# 06_-_JTAG.net
KiCad netlist of a schematic drawn in Altium Designer
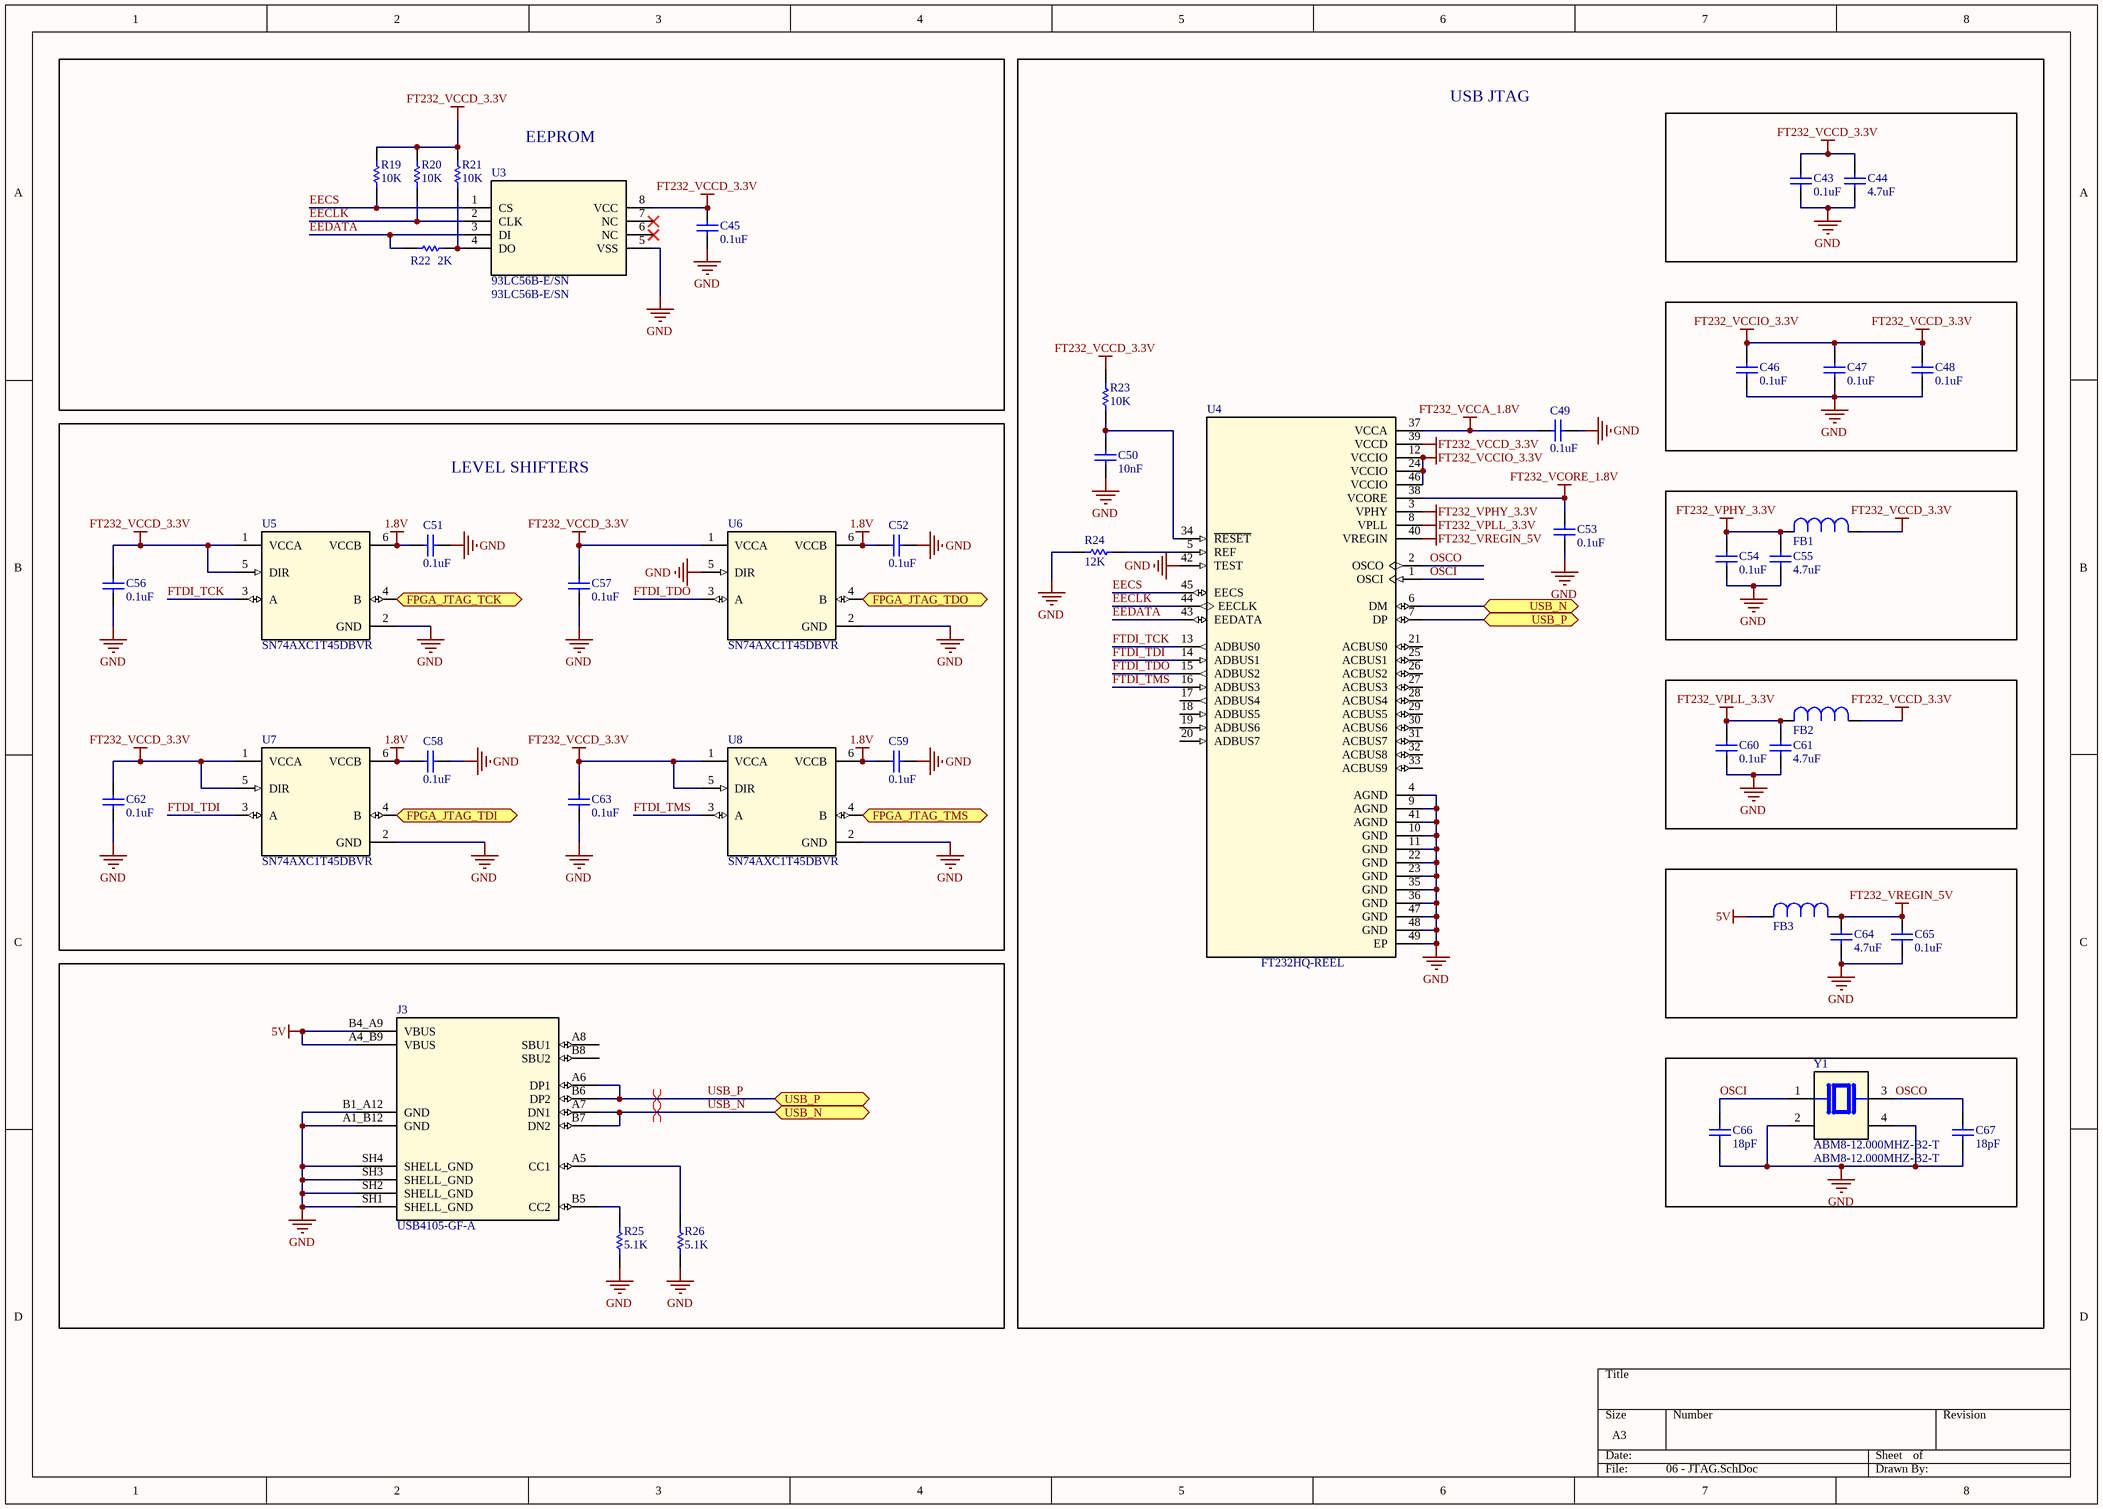
[diagram p0: 06 - JTAG.SchDoc]

(export (version "E")
  (design (tool "Eeschema 10.0.6"))
  (components
    (comp (ref "C43")
      (value "0.1uF")
      (footprint "0402-C-R")
      (description "0.1 µF ±10% 25V Ceramic Capacitor X5R 0402 (1005 Metric)")
      (fields (field (name "VOLTAGE") "25V") (field (name "TOLERANCE") "10%"))
      (libsource (lib "Schlib") (part "CAP CER 0.1UF 25V X5R 0402"))
    )
    (comp (ref "C44")
      (value "4.7uF")
      (footprint "0402-C-R")
      (description "CAP SMD 0402 MLCC GERAL 4.7uF 25V ±20% 0402 X5s PN: GRM155D81C475ME15J MURATA")
      (fields (field (name "VOLTAGE") "25V") (field (name "TOLERANCE") "20%"))
      (libsource (lib "Schlib") (part "CAP CER 4.7UF 10V X5R 0402"))
    )
    (comp (ref "C45")
      (value "0.1uF")
      (footprint "0402-C-R")
      (description "0.1 µF ±10% 25V Ceramic Capacitor X5R 0402 (1005 Metric)")
      (fields (field (name "VOLTAGE") "25V") (field (name "TOLERANCE") "10%"))
      (libsource (lib "Schlib") (part "CAP CER 0.1UF 25V X5R 0402"))
    )
    (comp (ref "C46")
      (value "0.1uF")
      (footprint "0402-C-R")
      (description "0.1 µF ±10% 25V Ceramic Capacitor X5R 0402 (1005 Metric)")
      (fields (field (name "VOLTAGE") "25V") (field (name "TOLERANCE") "10%"))
      (libsource (lib "Schlib") (part "CAP CER 0.1UF 25V X5R 0402"))
    )
    (comp (ref "C47")
      (value "0.1uF")
      (footprint "0402-C-R")
      (description "0.1 µF ±10% 25V Ceramic Capacitor X5R 0402 (1005 Metric)")
      (fields (field (name "VOLTAGE") "25V") (field (name "TOLERANCE") "10%"))
      (libsource (lib "Schlib") (part "CAP CER 0.1UF 25V X5R 0402"))
    )
    (comp (ref "C48")
      (value "0.1uF")
      (footprint "0402-C-R")
      (description "0.1 µF ±10% 25V Ceramic Capacitor X5R 0402 (1005 Metric)")
      (fields (field (name "VOLTAGE") "25V") (field (name "TOLERANCE") "10%"))
      (libsource (lib "Schlib") (part "CAP CER 0.1UF 25V X5R 0402"))
    )
    (comp (ref "C49")
      (value "0.1uF")
      (footprint "0402-C-R")
      (description "0.1 µF ±10% 25V Ceramic Capacitor X5R 0402 (1005 Metric)")
      (fields (field (name "VOLTAGE") "25V") (field (name "TOLERANCE") "10%"))
      (libsource (lib "Schlib") (part "CAP CER 0.1UF 25V X5R 0402"))
    )
    (comp (ref "C50")
      (value "10nF")
      (footprint "0402-C-R")
      (description "10000 pF ±10% 25V Ceramic Capacitor X7R 0402 (1005 Metric)")
      (fields (field (name "VOLTAGE") "25V") (field (name "TOLERANCE") "10%"))
      (libsource (lib "Schlib") (part "CAP CER 10nF 25V X7R 0402"))
    )
    (comp (ref "C51")
      (value "0.1uF")
      (footprint "0402-C-R")
      (description "0.1 µF ±10% 25V Ceramic Capacitor X5R 0402 (1005 Metric)")
      (fields (field (name "VOLTAGE") "25V") (field (name "TOLERANCE") "10%"))
      (libsource (lib "Schlib") (part "CAP CER 0.1UF 25V X5R 0402"))
    )
    (comp (ref "C52")
      (value "0.1uF")
      (footprint "0402-C-R")
      (description "0.1 µF ±10% 25V Ceramic Capacitor X5R 0402 (1005 Metric)")
      (fields (field (name "VOLTAGE") "25V") (field (name "TOLERANCE") "10%"))
      (libsource (lib "Schlib") (part "CAP CER 0.1UF 25V X5R 0402"))
    )
    (comp (ref "C53")
      (value "0.1uF")
      (footprint "0402-C-R")
      (description "0.1 µF ±10% 25V Ceramic Capacitor X5R 0402 (1005 Metric)")
      (fields (field (name "VOLTAGE") "25V") (field (name "TOLERANCE") "10%"))
      (libsource (lib "Schlib") (part "CAP CER 0.1UF 25V X5R 0402"))
    )
    (comp (ref "C54")
      (value "0.1uF")
      (footprint "0402-C-R")
      (description "0.1 µF ±10% 25V Ceramic Capacitor X5R 0402 (1005 Metric)")
      (fields (field (name "VOLTAGE") "25V") (field (name "TOLERANCE") "10%"))
      (libsource (lib "Schlib") (part "CAP CER 0.1UF 25V X5R 0402"))
    )
    (comp (ref "C55")
      (value "4.7uF")
      (footprint "0402-C-R")
      (description "CAP SMD 0402 MLCC GERAL 4.7uF 25V ±20% 0402 X5s PN: GRM155D81C475ME15J MURATA")
      (fields (field (name "VOLTAGE") "25V") (field (name "TOLERANCE") "20%"))
      (libsource (lib "Schlib") (part "CAP CER 4.7UF 25V X5R 0402"))
    )
    (comp (ref "C56")
      (value "0.1uF")
      (footprint "0402-C-R")
      (description "0.1 µF ±10% 25V Ceramic Capacitor X5R 0402 (1005 Metric)")
      (fields (field (name "VOLTAGE") "25V") (field (name "TOLERANCE") "10%"))
      (libsource (lib "Schlib") (part "CAP CER 0.1UF 25V X5R 0402"))
    )
    (comp (ref "C57")
      (value "0.1uF")
      (footprint "0402-C-R")
      (description "0.1 µF ±10% 25V Ceramic Capacitor X5R 0402 (1005 Metric)")
      (fields (field (name "VOLTAGE") "25V") (field (name "TOLERANCE") "10%"))
      (libsource (lib "Schlib") (part "CAP CER 0.1UF 25V X5R 0402"))
    )
    (comp (ref "C58")
      (value "0.1uF")
      (footprint "0402-C-R")
      (description "0.1 µF ±10% 25V Ceramic Capacitor X5R 0402 (1005 Metric)")
      (fields (field (name "VOLTAGE") "25V") (field (name "TOLERANCE") "10%"))
      (libsource (lib "Schlib") (part "CAP CER 0.1UF 25V X5R 0402"))
    )
    (comp (ref "C59")
      (value "0.1uF")
      (footprint "0402-C-R")
      (description "0.1 µF ±10% 25V Ceramic Capacitor X5R 0402 (1005 Metric)")
      (fields (field (name "VOLTAGE") "25V") (field (name "TOLERANCE") "10%"))
      (libsource (lib "Schlib") (part "CAP CER 0.1UF 25V X5R 0402"))
    )
    (comp (ref "C60")
      (value "0.1uF")
      (footprint "0402-C-R")
      (description "0.1 µF ±10% 25V Ceramic Capacitor X5R 0402 (1005 Metric)")
      (fields (field (name "VOLTAGE") "25V") (field (name "TOLERANCE") "10%"))
      (libsource (lib "Schlib") (part "CAP CER 0.1UF 25V X5R 0402"))
    )
    (comp (ref "C61")
      (value "4.7uF")
      (footprint "0402-C-R")
      (description "CAP SMD 0402 MLCC GERAL 4.7uF 25V ±20% 0402 X5s PN: GRM155D81C475ME15J MURATA")
      (fields (field (name "VOLTAGE") "25V") (field (name "TOLERANCE") "20%"))
      (libsource (lib "Schlib") (part "CAP CER 4.7UF 25V X5R 0402"))
    )
    (comp (ref "C62")
      (value "0.1uF")
      (footprint "0402-C-R")
      (description "0.1 µF ±10% 25V Ceramic Capacitor X5R 0402 (1005 Metric)")
      (fields (field (name "VOLTAGE") "25V") (field (name "TOLERANCE") "10%"))
      (libsource (lib "Schlib") (part "CAP CER 0.1UF 25V X5R 0402"))
    )
    (comp (ref "C63")
      (value "0.1uF")
      (footprint "0402-C-R")
      (description "0.1 µF ±10% 25V Ceramic Capacitor X5R 0402 (1005 Metric)")
      (fields (field (name "VOLTAGE") "25V") (field (name "TOLERANCE") "10%"))
      (libsource (lib "Schlib") (part "CAP CER 0.1UF 25V X5R 0402"))
    )
    (comp (ref "C64")
      (value "4.7uF")
      (footprint "0402-C-R")
      (description "CAP SMD 0402 MLCC GERAL 4.7uF 25V ±20% 0402 X5s PN: GRM155D81C475ME15J MURATA")
      (fields (field (name "VOLTAGE") "25V") (field (name "TOLERANCE") "20%"))
      (libsource (lib "Schlib") (part "CAP CER 4.7UF 25V X5R 0402"))
    )
    (comp (ref "C65")
      (value "0.1uF")
      (footprint "0402-C-R")
      (description "0.1 µF ±10% 25V Ceramic Capacitor X5R 0402 (1005 Metric)")
      (fields (field (name "VOLTAGE") "25V") (field (name "TOLERANCE") "10%"))
      (libsource (lib "Schlib") (part "CAP CER 0.1UF 25V X5R 0402"))
    )
    (comp (ref "C66")
      (value "18pF")
      (footprint "0402-C-R")
      (description "18 pF ±5% 50V Capacitor de cerâmica C0G, NP0 0402 (métrico 1005)PN:GRM1555C1H180JA01D MURATA")
      (fields (field (name "VOLTAGE") "50V") (field (name "TOLERANCE") "5%"))
      (libsource (lib "Schlib") (part "CAP CER 18PF 50V C0G/NP0 0402"))
    )
    (comp (ref "C67")
      (value "18pF")
      (footprint "0402-C-R")
      (description "18 pF ±5% 50V Capacitor de cerâmica C0G, NP0 0402 (métrico 1005)PN:GRM1555C1H180JA01D MURATA")
      (fields (field (name "VOLTAGE") "50V") (field (name "TOLERANCE") "5%"))
      (libsource (lib "Schlib") (part "CAP CER 18PF 50V C0G/NP0 0402"))
    )
    (comp (ref "FB1")
      (value "BLM15HD182SN1D")
      (footprint "0402-F-R")
      (description "FERRITE BEAD 1.8K OHM 0402 1LN PN: BLM15HD182SN1D")
      (libsource (lib "Schlib") (part "FERRITE BEAD 1.8K OHM 0402 1LN"))
    )
    (comp (ref "FB2")
      (value "BLM15HD182SN1D")
      (footprint "0402-F-R")
      (description "FERRITE BEAD 1.8K OHM 0402 1LN PN: BLM15HD182SN1D")
      (libsource (lib "Schlib") (part "FERRITE BEAD 1.8K OHM 0402 1LN"))
    )
    (comp (ref "FB3")
      (value "BLM15HD182SN1D")
      (footprint "0402-F-R")
      (description "FERRITE BEAD 1.8K OHM 0402 1LN PN: BLM15HD182SN1D")
      (libsource (lib "Schlib") (part "FERRITE BEAD 1.8K OHM 0402 1LN"))
    )
    (comp (ref "J3")
      (value "CONN RCP USB2.0 TYP C 24P SMD RA")
      (footprint "GCT_USB4105-GF-A")
      (description "CONN RCP USB2.0 TYP C 24P SMD RA PN: USB4105-GF-A")
      (fields (field (name "MF") "{'manufacturer': u'GCT'}") (field (name "PN") "USB4105-GF-A"))
      (libsource (lib "Schlib") (part "CONN RCP USB2.0 TYP C 24P SMD RA"))
    )
    (comp (ref "R19")
      (value "10K")
      (footprint "0402-R-R")
      (description "10 kOhms ±1% 0,063W, 1/16W Resistor de chip 0402 (métrico 1005) Resistente à umidade Filme grosso")
      (fields (field (name "POWER") "0.063W") (field (name "TOLERANCE") "1%"))
      (libsource (lib "Schlib") (part "RES 10K OHM 1% 1/16W 0402"))
    )
    (comp (ref "R20")
      (value "10K")
      (footprint "0402-R-R")
      (description "10 kOhms ±1% 0,063W, 1/16W Resistor de chip 0402 (métrico 1005) Resistente à umidade Filme grosso")
      (fields (field (name "POWER") "0.063W") (field (name "TOLERANCE") "1%"))
      (libsource (lib "Schlib") (part "RES 10K OHM 1% 1/16W 0402"))
    )
    (comp (ref "R21")
      (value "10K")
      (footprint "0402-R-R")
      (description "10 kOhms ±1% 0,063W, 1/16W Resistor de chip 0402 (métrico 1005) Resistente à umidade Filme grosso")
      (fields (field (name "POWER") "0.063W") (field (name "TOLERANCE") "1%"))
      (libsource (lib "Schlib") (part "RES 10K OHM 1% 1/16W 0402"))
    )
    (comp (ref "R22")
      (value "2K")
      (footprint "0402-R-R")
      (description "RES SMD GERAL FILM 2K 0.063W ±1% 0402 7\" TAPE PN: RMCF0402FT2K00 STACKPOLE")
      (fields (field (name "POWER") "0.063W") (field (name "TOLERANCE") "1%"))
      (libsource (lib "Schlib") (part "RES SMD 0402 2K 0.063W ±1%"))
    )
    (comp (ref "R23")
      (value "10K")
      (footprint "0402-R-R")
      (description "10 kOhms ±1% 0,063W, 1/16W Resistor de chip 0402 (métrico 1005) Resistente à umidade Filme grosso")
      (fields (field (name "POWER") "0.063W") (field (name "TOLERANCE") "1%"))
      (libsource (lib "Schlib") (part "RES 10K OHM 1% 1/16W 0402"))
    )
    (comp (ref "R24")
      (value "12K")
      (footprint "0402-R-R")
      (description "RES SMD GERAL FILM 12K 0.063W ±1% 0402 7\" TAPE PN: RMCF0402FT12K0")
      (fields (field (name "POWER") "0.063W") (field (name "TOLERANCE") "1%"))
      (libsource (lib "Schlib") (part "RES SMD 0402 12K 0.063W ±1%"))
    )
    (comp (ref "R25")
      (value "5.1K")
      (footprint "0402-R-R")
      (description "RES SMD 0402 5.1K OHM 1% 1/16W 0402 PN: RMCF0402FT5K10")
      (fields (field (name "TOLERANCE") "0.1%") (field (name "POWER") "0.063W"))
      (libsource (lib "Schlib") (part "RES SMD 0402 5.1K OHM 1% 1/16W"))
    )
    (comp (ref "R26")
      (value "5.1K")
      (footprint "0402-R-R")
      (description "RES SMD 0402 5.1K OHM 1% 1/16W 0402 PN: RMCF0402FT5K10")
      (fields (field (name "TOLERANCE") "0.1%") (field (name "POWER") "0.063W"))
      (libsource (lib "Schlib") (part "RES SMD 0402 5.1K OHM 1% 1/16W"))
    )
    (comp (ref "U3")
      (value "93LC56B-E/SN")
      (footprint "93LC56B-E/SN")
      (description "EEPROM CI de memória 2Kbit Microwire 2 MHz 8-SOIC. PN: 93LC56B-E/SN")
      (fields (field (name "PN") "93LC56B-E/SN"))
      (libsource (lib "Schlib") (part "IC EEPROM 2KBIT MICROWIRE 8SOIC"))
    )
    (comp (ref "U4")
      (value "IC HS USB TO UART/FIFO 48QFN")
      (footprint "FT232HQ")
      (description "USB Bridge, USB to UART,FIFO USB 2.0 UART, FIFO Interface 48-QFN (8x8) PN: FT232HQ-REEL")
      (fields
        (field (name "MP") "FT232HQ-REEL")
        (field (name "MF") "FTDI, Future")
        (field (name "PN") "FT232HQ-REEL")
      )
      (libsource (lib "Schlib") (part "IC HS USB TO UART/FIFO 48QFN"))
    )
    (comp (ref "U5")
      (value "SN74AXC1T45DBVR")
      (footprint "SN74AXC1T45DBVR")
      (description "Nível de tensão Tradutor Bidirecional 1 Circuito 1 Canal 500Mbps SOT-23-6. PN: SN74AXC1T45DBVR")
      (fields (field (name "MF") "Texas Instruments") (field (name "PN") "SN74AXC1T45DBVR"))
      (libsource (lib "Schlib") (part "IC TRANSLATOR BIDIR SOT23-6"))
    )
    (comp (ref "U6")
      (value "SN74AXC1T45DBVR")
      (footprint "SN74AXC1T45DBVR")
      (description "Nível de tensão Tradutor Bidirecional 1 Circuito 1 Canal 500Mbps SOT-23-6. PN: SN74AXC1T45DBVR")
      (fields (field (name "MF") "Texas Instruments") (field (name "PN") "SN74AXC1T45DBVR"))
      (libsource (lib "Schlib") (part "IC TRANSLATOR BIDIR SOT23-6"))
    )
    (comp (ref "U7")
      (value "SN74AXC1T45DBVR")
      (footprint "SN74AXC1T45DBVR")
      (description "Nível de tensão Tradutor Bidirecional 1 Circuito 1 Canal 500Mbps SOT-23-6. PN: SN74AXC1T45DBVR")
      (fields (field (name "MF") "Texas Instruments") (field (name "PN") "SN74AXC1T45DBVR"))
      (libsource (lib "Schlib") (part "IC TRANSLATOR BIDIR SOT23-6"))
    )
    (comp (ref "U8")
      (value "SN74AXC1T45DBVR")
      (footprint "SN74AXC1T45DBVR")
      (description "Nível de tensão Tradutor Bidirecional 1 Circuito 1 Canal 500Mbps SOT-23-6. PN: SN74AXC1T45DBVR")
      (fields (field (name "MF") "Texas Instruments") (field (name "PN") "SN74AXC1T45DBVR"))
      (libsource (lib "Schlib") (part "IC TRANSLATOR BIDIR SOT23-6"))
    )
    (comp (ref "Y1")
      (value "ABM8-12.000MHZ-B2-T")
      (footprint "XTAL_ABM8-12.000MHZ-B2-T")
      (description "12 MHz ±20ppm Cristal 18pF 120 Ohms 4-SMD, sem condutores PN: ABM8-12.000MHZ-B2-T")
      (fields (field (name "MF") "Abracon") (field (name "PN") "ABM8-12.000MHZ-B2-T"))
      (libsource (lib "Schlib") (part "CRYSTAL 12.0000MHZ 18PF SMD"))
    )
  )
  (nets
    (net (code "1") (name "/EECLK") (class "Default")
      (node (ref "R20") (pin "1") (pinfunction "1_1") (pintype "passive"))
      (node (ref "U3") (pin "2") (pinfunction "CLK_2") (pintype "passive"))
      (node (ref "U4") (pin "44") (pinfunction "EECLK_44") (pintype "output"))
    )
    (net (code "2") (name "/EECS") (class "Default")
      (node (ref "R19") (pin "1") (pinfunction "1_1") (pintype "passive"))
      (node (ref "U3") (pin "1") (pinfunction "CS_1") (pintype "passive"))
      (node (ref "U4") (pin "45") (pinfunction "EECS_45") (pintype "bidirectional"))
    )
    (net (code "3") (name "/EEDATA") (class "Default")
      (node (ref "R22") (pin "1") (pinfunction "1_1") (pintype "passive"))
      (node (ref "U3") (pin "3") (pinfunction "DI_3") (pintype "passive"))
      (node (ref "U4") (pin "43") (pinfunction "EEDATA_43") (pintype "bidirectional"))
    )
    (net (code "4") (name "/FPGA_JTAG_TCK") (class "Default")
      (node (ref "U5") (pin "4") (pinfunction "B_4") (pintype "bidirectional"))
    )
    (net (code "5") (name "/FPGA_JTAG_TDI") (class "Default")
      (node (ref "U7") (pin "4") (pinfunction "B_4") (pintype "bidirectional"))
    )
    (net (code "6") (name "/FPGA_JTAG_TDO") (class "Default")
      (node (ref "U6") (pin "4") (pinfunction "B_4") (pintype "bidirectional"))
    )
    (net (code "7") (name "/FPGA_JTAG_TMS") (class "Default")
      (node (ref "U8") (pin "4") (pinfunction "B_4") (pintype "bidirectional"))
    )
    (net (code "8") (name "/FTDI_TCK") (class "Default")
      (node (ref "U4") (pin "13") (pinfunction "ADBUS0_13") (pintype "output"))
      (node (ref "U5") (pin "3") (pinfunction "A_3") (pintype "bidirectional"))
    )
    (net (code "9") (name "/FTDI_TDI") (class "Default")
      (node (ref "U4") (pin "14") (pinfunction "ADBUS1_14") (pintype "input"))
      (node (ref "U7") (pin "3") (pinfunction "A_3") (pintype "bidirectional"))
    )
    (net (code "10") (name "/FTDI_TDO") (class "Default")
      (node (ref "U4") (pin "15") (pinfunction "ADBUS2_15") (pintype "output"))
      (node (ref "U6") (pin "3") (pinfunction "A_3") (pintype "bidirectional"))
    )
    (net (code "11") (name "/FTDI_TMS") (class "Default")
      (node (ref "U4") (pin "16") (pinfunction "ADBUS3_16") (pintype "input"))
      (node (ref "U8") (pin "3") (pinfunction "A_3") (pintype "bidirectional"))
    )
    (net (code "12") (name "/OSCI") (class "Default")
      (node (ref "C66") (pin "2") (pinfunction "2_2") (pintype "passive"))
      (node (ref "U4") (pin "1") (pinfunction "OSCI_1") (pintype "input"))
      (node (ref "Y1") (pin "1") (pinfunction "1_1") (pintype "passive"))
    )
    (net (code "13") (name "/OSCO") (class "Default")
      (node (ref "C67") (pin "2") (pinfunction "2_2") (pintype "passive"))
      (node (ref "U4") (pin "2") (pinfunction "OSCO_2") (pintype "output"))
      (node (ref "Y1") (pin "3") (pinfunction "2_3") (pintype "passive"))
    )
    (net (code "14") (name "/USB_N") (class "Default")
      (node (ref "J3") (pin "A7") (pinfunction "DN1_A7") (pintype "bidirectional"))
      (node (ref "J3") (pin "B7") (pinfunction "DN2_B7") (pintype "bidirectional"))
      (node (ref "U4") (pin "6") (pinfunction "DM_6") (pintype "bidirectional"))
    )
    (net (code "15") (name "/USB_P") (class "Default")
      (node (ref "J3") (pin "A6") (pinfunction "DP1_A6") (pintype "bidirectional"))
      (node (ref "J3") (pin "B6") (pinfunction "DP2_B6") (pintype "bidirectional"))
      (node (ref "U4") (pin "7") (pinfunction "DP_7") (pintype "bidirectional"))
    )
    (net (code "16") (name "1.8V") (class "Default")
      (node (ref "C51") (pin "2") (pinfunction "2_2") (pintype "passive"))
      (node (ref "C52") (pin "2") (pinfunction "2_2") (pintype "passive"))
      (node (ref "C58") (pin "2") (pinfunction "2_2") (pintype "passive"))
      (node (ref "C59") (pin "2") (pinfunction "2_2") (pintype "passive"))
      (node (ref "U5") (pin "6") (pinfunction "VCCB_6") (pintype "power_in"))
      (node (ref "U6") (pin "6") (pinfunction "VCCB_6") (pintype "power_in"))
      (node (ref "U7") (pin "6") (pinfunction "VCCB_6") (pintype "power_in"))
      (node (ref "U8") (pin "6") (pinfunction "VCCB_6") (pintype "power_in"))
    )
    (net (code "17") (name "5V") (class "Default")
      (node (ref "FB3") (pin "2") (pinfunction "2_2") (pintype "passive"))
      (node (ref "J3") (pin "A4_B9") (pinfunction "VBUS_A4_B9") (pintype "power_in"))
      (node (ref "J3") (pin "B4_A9") (pinfunction "VBUS_B4_A9") (pintype "power_in"))
    )
    (net (code "18") (name "FT232_VCCA_1.8V") (class "Default")
      (node (ref "C49") (pin "2") (pinfunction "2_2") (pintype "passive"))
      (node (ref "U4") (pin "37") (pinfunction "VCCA_37") (pintype "power_in"))
    )
    (net (code "19") (name "FT232_VCCD_3.3V") (class "Default")
      (node (ref "C43") (pin "2") (pinfunction "2_2") (pintype "passive"))
      (node (ref "C44") (pin "2") (pinfunction "2_2") (pintype "passive"))
      (node (ref "C45") (pin "2") (pinfunction "2_2") (pintype "passive"))
      (node (ref "C46") (pin "2") (pinfunction "2_2") (pintype "passive"))
      (node (ref "C47") (pin "2") (pinfunction "2_2") (pintype "passive"))
      (node (ref "C48") (pin "2") (pinfunction "2_2") (pintype "passive"))
      (node (ref "C56") (pin "2") (pinfunction "2_2") (pintype "passive"))
      (node (ref "C57") (pin "2") (pinfunction "2_2") (pintype "passive"))
      (node (ref "C62") (pin "2") (pinfunction "2_2") (pintype "passive"))
      (node (ref "C63") (pin "2") (pinfunction "2_2") (pintype "passive"))
      (node (ref "FB1") (pin "1") (pinfunction "1_1") (pintype "passive"))
      (node (ref "FB2") (pin "1") (pinfunction "1_1") (pintype "passive"))
      (node (ref "R19") (pin "2") (pinfunction "2_2") (pintype "passive"))
      (node (ref "R20") (pin "2") (pinfunction "2_2") (pintype "passive"))
      (node (ref "R21") (pin "2") (pinfunction "2_2") (pintype "passive"))
      (node (ref "R23") (pin "2") (pinfunction "2_2") (pintype "passive"))
      (node (ref "U3") (pin "8") (pinfunction "VCC_8") (pintype "passive"))
      (node (ref "U4") (pin "12") (pinfunction "VCCIO_12") (pintype "power_in"))
      (node (ref "U4") (pin "24") (pinfunction "VCCIO_24") (pintype "power_in"))
      (node (ref "U4") (pin "39") (pinfunction "VCCD_39") (pintype "power_in"))
      (node (ref "U4") (pin "46") (pinfunction "VCCIO_46") (pintype "power_in"))
      (node (ref "U5") (pin "1") (pinfunction "VCCA_1") (pintype "power_in"))
      (node (ref "U5") (pin "5") (pinfunction "DIR_5") (pintype "input"))
      (node (ref "U6") (pin "1") (pinfunction "VCCA_1") (pintype "power_in"))
      (node (ref "U7") (pin "1") (pinfunction "VCCA_1") (pintype "power_in"))
      (node (ref "U7") (pin "5") (pinfunction "DIR_5") (pintype "input"))
      (node (ref "U8") (pin "1") (pinfunction "VCCA_1") (pintype "power_in"))
      (node (ref "U8") (pin "5") (pinfunction "DIR_5") (pintype "input"))
    )
    (net (code "20") (name "FT232_VCORE_1.8V") (class "Default")
      (node (ref "C53") (pin "1") (pinfunction "1_1") (pintype "passive"))
      (node (ref "U4") (pin "38") (pinfunction "VCORE_38") (pintype "power_in"))
    )
    (net (code "21") (name "FT232_VPHY_3.3V") (class "Default")
      (node (ref "C54") (pin "2") (pinfunction "2_2") (pintype "passive"))
      (node (ref "C55") (pin "2") (pinfunction "2_2") (pintype "passive"))
      (node (ref "FB1") (pin "2") (pinfunction "2_2") (pintype "passive"))
      (node (ref "U4") (pin "3") (pinfunction "VPHY_3") (pintype "power_in"))
    )
    (net (code "22") (name "FT232_VPLL_3.3V") (class "Default")
      (node (ref "C60") (pin "2") (pinfunction "2_2") (pintype "passive"))
      (node (ref "C61") (pin "2") (pinfunction "2_2") (pintype "passive"))
      (node (ref "FB2") (pin "2") (pinfunction "2_2") (pintype "passive"))
      (node (ref "U4") (pin "8") (pinfunction "VPLL_8") (pintype "power_in"))
    )
    (net (code "23") (name "FT232_VREGIN_5V") (class "Default")
      (node (ref "C64") (pin "2") (pinfunction "2_2") (pintype "passive"))
      (node (ref "C65") (pin "2") (pinfunction "2_2") (pintype "passive"))
      (node (ref "FB3") (pin "1") (pinfunction "1_1") (pintype "passive"))
      (node (ref "U4") (pin "40") (pinfunction "VREGIN_40") (pintype "power_in"))
    )
    (net (code "24") (name "GND") (class "Default")
      (node (ref "C43") (pin "1") (pinfunction "1_1") (pintype "passive"))
      (node (ref "C44") (pin "1") (pinfunction "1_1") (pintype "passive"))
      (node (ref "C45") (pin "1") (pinfunction "1_1") (pintype "passive"))
      (node (ref "C46") (pin "1") (pinfunction "1_1") (pintype "passive"))
      (node (ref "C47") (pin "1") (pinfunction "1_1") (pintype "passive"))
      (node (ref "C48") (pin "1") (pinfunction "1_1") (pintype "passive"))
      (node (ref "C49") (pin "1") (pinfunction "1_1") (pintype "passive"))
      (node (ref "C50") (pin "1") (pinfunction "1_1") (pintype "passive"))
      (node (ref "C51") (pin "1") (pinfunction "1_1") (pintype "passive"))
      (node (ref "C52") (pin "1") (pinfunction "1_1") (pintype "passive"))
      (node (ref "C53") (pin "2") (pinfunction "2_2") (pintype "passive"))
      (node (ref "C54") (pin "1") (pinfunction "1_1") (pintype "passive"))
      (node (ref "C55") (pin "1") (pinfunction "1_1") (pintype "passive"))
      (node (ref "C56") (pin "1") (pinfunction "1_1") (pintype "passive"))
      (node (ref "C57") (pin "1") (pinfunction "1_1") (pintype "passive"))
      (node (ref "C58") (pin "1") (pinfunction "1_1") (pintype "passive"))
      (node (ref "C59") (pin "1") (pinfunction "1_1") (pintype "passive"))
      (node (ref "C60") (pin "1") (pinfunction "1_1") (pintype "passive"))
      (node (ref "C61") (pin "1") (pinfunction "1_1") (pintype "passive"))
      (node (ref "C62") (pin "1") (pinfunction "1_1") (pintype "passive"))
      (node (ref "C63") (pin "1") (pinfunction "1_1") (pintype "passive"))
      (node (ref "C64") (pin "1") (pinfunction "1_1") (pintype "passive"))
      (node (ref "C65") (pin "1") (pinfunction "1_1") (pintype "passive"))
      (node (ref "C66") (pin "1") (pinfunction "1_1") (pintype "passive"))
      (node (ref "C67") (pin "1") (pinfunction "1_1") (pintype "passive"))
      (node (ref "J3") (pin "A1_B12") (pinfunction "GND_A1_B12") (pintype "power_in"))
      (node (ref "J3") (pin "B1_A12") (pinfunction "GND_B1_A12") (pintype "power_in"))
      (node (ref "J3") (pin "SH1") (pinfunction "SHELL_GND_SH1") (pintype "power_in"))
      (node (ref "J3") (pin "SH2") (pinfunction "SHELL_GND_SH2") (pintype "power_in"))
      (node (ref "J3") (pin "SH3") (pinfunction "SHELL_GND_SH3") (pintype "power_in"))
      (node (ref "J3") (pin "SH4") (pinfunction "SHELL_GND_SH4") (pintype "power_in"))
      (node (ref "R24") (pin "1") (pinfunction "1_1") (pintype "passive"))
      (node (ref "R25") (pin "1") (pinfunction "1_1") (pintype "passive"))
      (node (ref "R26") (pin "1") (pinfunction "1_1") (pintype "passive"))
      (node (ref "U3") (pin "5") (pinfunction "VSS_5") (pintype "passive"))
      (node (ref "U4") (pin "10") (pinfunction "GND_10") (pintype "power_in"))
      (node (ref "U4") (pin "11") (pinfunction "GND_11") (pintype "power_in"))
      (node (ref "U4") (pin "22") (pinfunction "GND_22") (pintype "power_in"))
      (node (ref "U4") (pin "23") (pinfunction "GND_23") (pintype "power_in"))
      (node (ref "U4") (pin "35") (pinfunction "GND_35") (pintype "power_in"))
      (node (ref "U4") (pin "36") (pinfunction "GND_36") (pintype "power_in"))
      (node (ref "U4") (pin "4") (pinfunction "AGND_4") (pintype "power_in"))
      (node (ref "U4") (pin "41") (pinfunction "AGND_41") (pintype "power_in"))
      (node (ref "U4") (pin "42") (pinfunction "TEST_42") (pintype "input"))
      (node (ref "U4") (pin "47") (pinfunction "GND_47") (pintype "power_in"))
      (node (ref "U4") (pin "48") (pinfunction "GND_48") (pintype "power_in"))
      (node (ref "U4") (pin "49") (pinfunction "EP_49") (pintype "power_in"))
      (node (ref "U4") (pin "9") (pinfunction "AGND_9") (pintype "power_in"))
      (node (ref "U5") (pin "2") (pinfunction "GND_2") (pintype "power_in"))
      (node (ref "U6") (pin "2") (pinfunction "GND_2") (pintype "power_in"))
      (node (ref "U6") (pin "5") (pinfunction "DIR_5") (pintype "input"))
      (node (ref "U7") (pin "2") (pinfunction "GND_2") (pintype "power_in"))
      (node (ref "U8") (pin "2") (pinfunction "GND_2") (pintype "power_in"))
      (node (ref "Y1") (pin "2") (pinfunction "GND_2") (pintype "power_in"))
      (node (ref "Y1") (pin "4") (pinfunction "GND_4") (pintype "power_in"))
    )
    (net (code "25") (name "Net-(J3-CC1)") (class "Default")
      (node (ref "J3") (pin "A5") (pinfunction "CC1_A5") (pintype "bidirectional"))
      (node (ref "R26") (pin "2") (pinfunction "2_2") (pintype "passive"))
    )
    (net (code "26") (name "Net-(J3-CC2)") (class "Default")
      (node (ref "J3") (pin "B5") (pinfunction "CC2_B5") (pintype "bidirectional"))
      (node (ref "R25") (pin "2") (pinfunction "2_2") (pintype "passive"))
    )
    (net (code "27") (name "Net-(U3-DO)") (class "Default")
      (node (ref "R21") (pin "1") (pinfunction "1_1") (pintype "passive"))
      (node (ref "R22") (pin "2") (pinfunction "2_2") (pintype "passive"))
      (node (ref "U3") (pin "4") (pinfunction "DO_4") (pintype "passive"))
    )
    (net (code "28") (name "Net-(U4-REF)") (class "Default")
      (node (ref "R24") (pin "2") (pinfunction "2_2") (pintype "passive"))
      (node (ref "U4") (pin "5") (pinfunction "REF_5") (pintype "input"))
    )
    (net (code "29") (name "Net-(U4-~{RESET})") (class "Default")
      (node (ref "C50") (pin "2") (pinfunction "2_2") (pintype "passive"))
      (node (ref "R23") (pin "1") (pinfunction "1_1") (pintype "passive"))
      (node (ref "U4") (pin "34") (pinfunction "~{RESET}_34") (pintype "input"))
    )
    (net (code "30") (name "unconnected-(J3-SBU1-PadA8)") (class "Default")
      (node (ref "J3") (pin "A8") (pinfunction "SBU1_A8") (pintype "bidirectional"))
    )
    (net (code "31") (name "unconnected-(J3-SBU2-PadB8)") (class "Default")
      (node (ref "J3") (pin "B8") (pinfunction "SBU2_B8") (pintype "bidirectional"))
    )
    (net (code "32") (name "unconnected-(U3-NC-Pad6)") (class "Default")
      (node (ref "U3") (pin "6") (pinfunction "NC_6") (pintype "passive+no_connect"))
    )
    (net (code "33") (name "unconnected-(U3-NC-Pad7)") (class "Default")
      (node (ref "U3") (pin "7") (pinfunction "NC_7") (pintype "passive+no_connect"))
    )
    (net (code "34") (name "unconnected-(U4-ACBUS0-Pad21)") (class "Default")
      (node (ref "U4") (pin "21") (pinfunction "ACBUS0_21") (pintype "bidirectional"))
    )
    (net (code "35") (name "unconnected-(U4-ACBUS1-Pad25)") (class "Default")
      (node (ref "U4") (pin "25") (pinfunction "ACBUS1_25") (pintype "bidirectional"))
    )
    (net (code "36") (name "unconnected-(U4-ACBUS2-Pad26)") (class "Default")
      (node (ref "U4") (pin "26") (pinfunction "ACBUS2_26") (pintype "bidirectional"))
    )
    (net (code "37") (name "unconnected-(U4-ACBUS3-Pad27)") (class "Default")
      (node (ref "U4") (pin "27") (pinfunction "ACBUS3_27") (pintype "bidirectional"))
    )
    (net (code "38") (name "unconnected-(U4-ACBUS4-Pad28)") (class "Default")
      (node (ref "U4") (pin "28") (pinfunction "ACBUS4_28") (pintype "bidirectional"))
    )
    (net (code "39") (name "unconnected-(U4-ACBUS5-Pad29)") (class "Default")
      (node (ref "U4") (pin "29") (pinfunction "ACBUS5_29") (pintype "bidirectional"))
    )
    (net (code "40") (name "unconnected-(U4-ACBUS6-Pad30)") (class "Default")
      (node (ref "U4") (pin "30") (pinfunction "ACBUS6_30") (pintype "bidirectional"))
    )
    (net (code "41") (name "unconnected-(U4-ACBUS7-Pad31)") (class "Default")
      (node (ref "U4") (pin "31") (pinfunction "ACBUS7_31") (pintype "bidirectional"))
    )
    (net (code "42") (name "unconnected-(U4-ACBUS8-Pad32)") (class "Default")
      (node (ref "U4") (pin "32") (pinfunction "ACBUS8_32") (pintype "bidirectional"))
    )
    (net (code "43") (name "unconnected-(U4-ACBUS9-Pad33)") (class "Default")
      (node (ref "U4") (pin "33") (pinfunction "ACBUS9_33") (pintype "bidirectional"))
    )
    (net (code "44") (name "unconnected-(U4-ADBUS4-Pad17)") (class "Default")
      (node (ref "U4") (pin "17") (pinfunction "ADBUS4_17") (pintype "output"))
    )
    (net (code "45") (name "unconnected-(U4-ADBUS5-Pad18)") (class "Default")
      (node (ref "U4") (pin "18") (pinfunction "ADBUS5_18") (pintype "input"))
    )
    (net (code "46") (name "unconnected-(U4-ADBUS6-Pad19)") (class "Default")
      (node (ref "U4") (pin "19") (pinfunction "ADBUS6_19") (pintype "input"))
    )
    (net (code "47") (name "unconnected-(U4-ADBUS7-Pad20)") (class "Default")
      (node (ref "U4") (pin "20") (pinfunction "ADBUS7_20") (pintype "input"))
    )
  )
)
